# Sheet2.net
KiCad netlist of a schematic drawn in Altium Designer
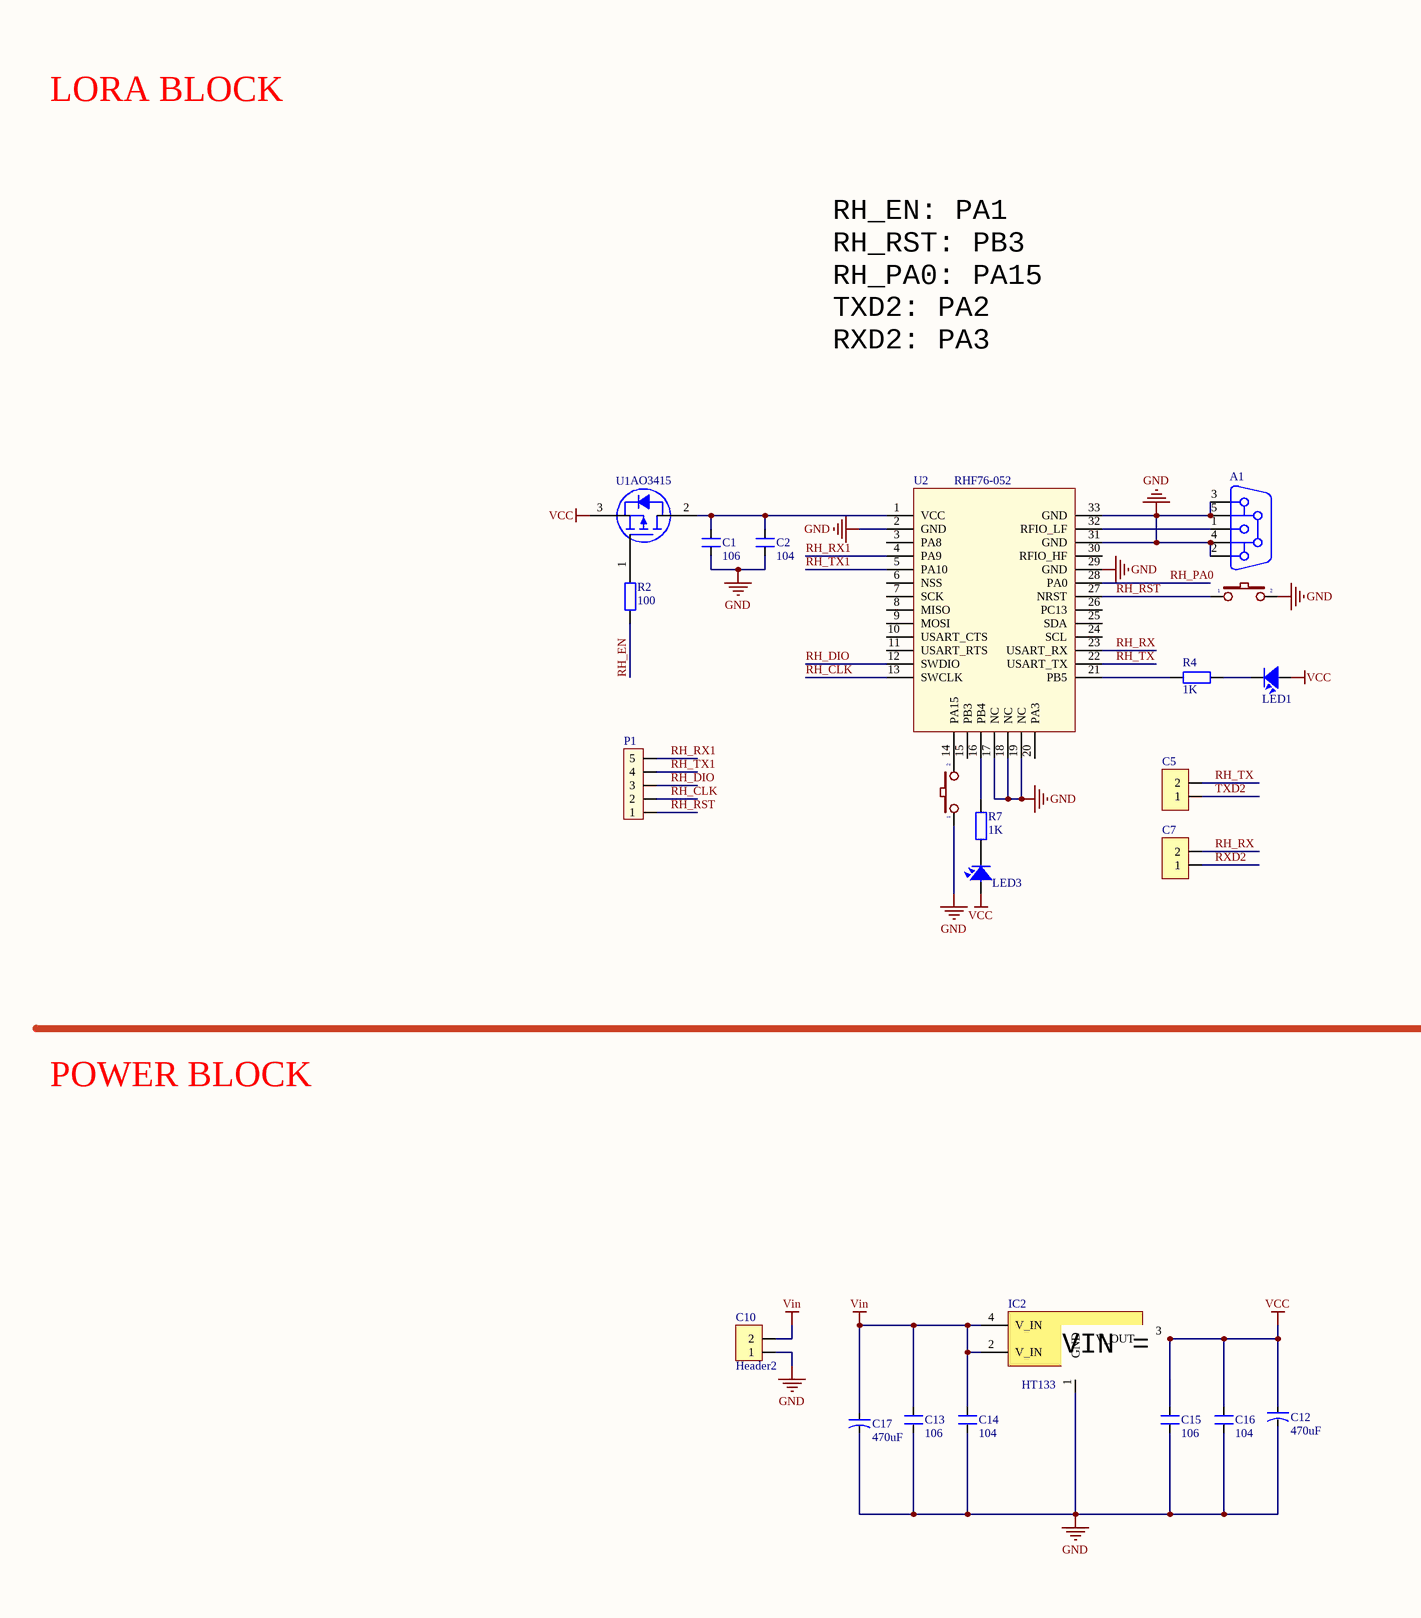
[diagram p0: Sheet2.SchDoc, left]
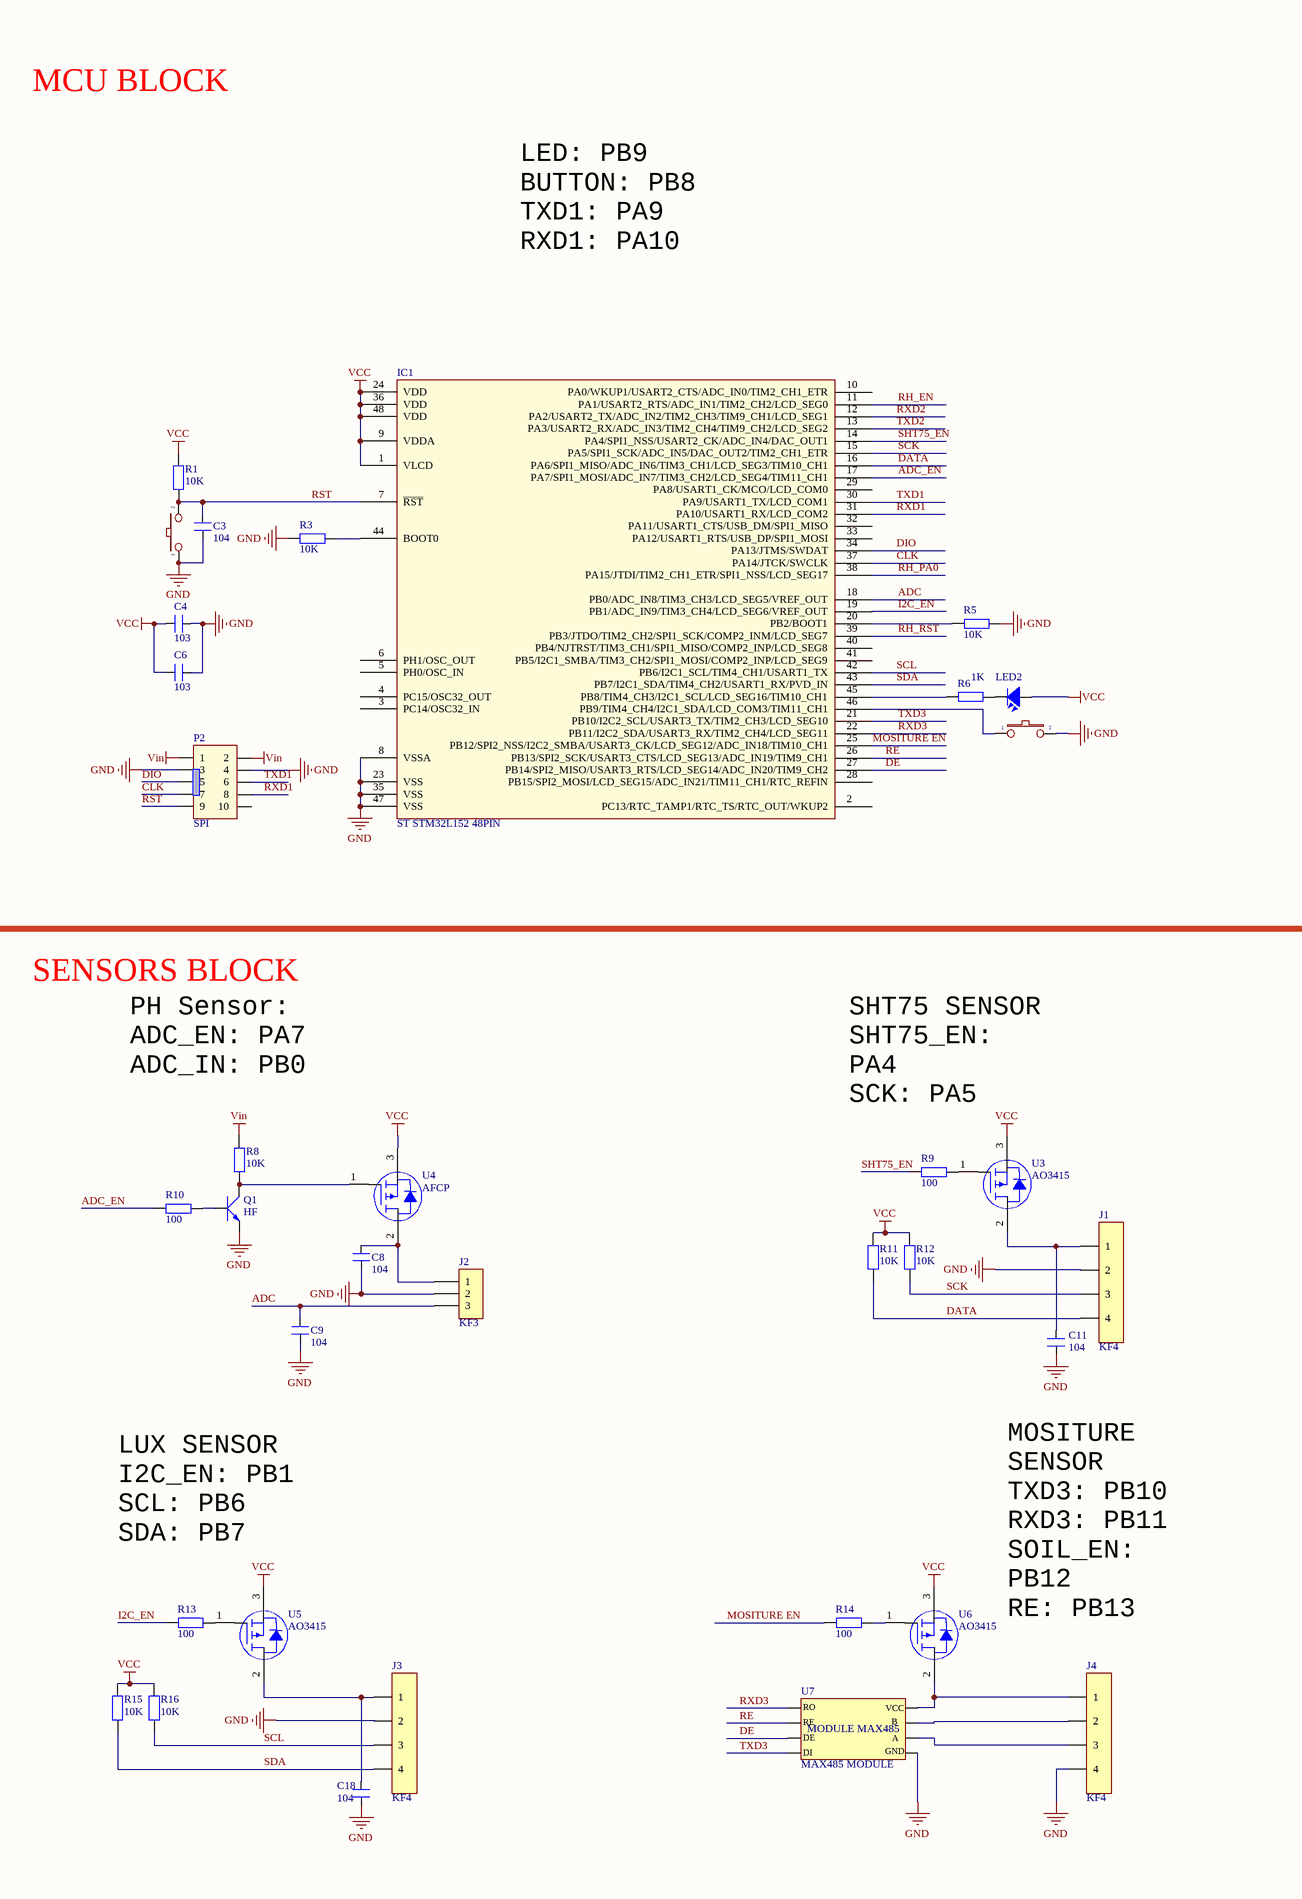
[diagram p1: Sheet2.SchDoc, right]

(export (version "E")
  (design (tool "Eeschema 10.0.6"))
  (components
    (comp (ref "A1")
      (value "~")
      (footprint "SMA-V")
      (description "CONNECTOR ANTEN")
      (fields
        (field (name "PARTNO") "210111003")
        (field (name "MANUFACTURER") "Würth Elektronik eiSos GmbH")
        (field (name "CREATED BY") "Christin Zierenner")
      )
      (libsource (lib "LIBRARY") (part "CON Ant"))
    )
    (comp (ref "C1")
      (value "106")
      (footprint "CAP 0805")
      (description "Cap SMD")
      (libsource (lib "linhkien69") (part "CM"))
    )
    (comp (ref "C2")
      (value "104")
      (footprint "CAP 0805")
      (description "Cap SMD")
      (libsource (lib "linhkien69") (part "CM"))
    )
    (comp (ref "C3")
      (value "104")
      (footprint "CAP 0805")
      (description "Cap SMD")
      (libsource (lib "linhkien69") (part "CM"))
    )
    (comp (ref "C4")
      (value "103")
      (footprint "CAP 0805")
      (description "Cap SMD")
      (libsource (lib "linhkien69") (part "CM"))
    )
    (comp (ref "C5")
      (value "JP2")
      (footprint "JP2-CLOSED")
      (description "WR-PHD 2.54 mm Angled Socket Header")
      (fields
        (field (name "MANUFACTURER") "Würth Elektronik eiSos GmbH")
        (field (name "PARTNO") "613002143121")
        (field (name "CREATED BY") "Karrer Zheng")
      )
      (libsource (lib "LIBRARY") (part "JP2"))
    )
    (comp (ref "C6")
      (value "103")
      (footprint "CAP 0805")
      (description "Cap SMD")
      (libsource (lib "linhkien69") (part "CM"))
    )
    (comp (ref "C7")
      (value "JP2")
      (footprint "JP2-CLOSED")
      (description "WR-PHD 2.54 mm Angled Socket Header")
      (fields
        (field (name "MANUFACTURER") "Würth Elektronik eiSos GmbH")
        (field (name "PARTNO") "613002143121")
        (field (name "CREATED BY") "Karrer Zheng")
      )
      (libsource (lib "LIBRARY") (part "JP2"))
    )
    (comp (ref "C8")
      (value "104")
      (footprint "CAP 0805")
      (description "Cap SMD")
      (libsource (lib "linhkien69") (part "CM"))
    )
    (comp (ref "C9")
      (value "104")
      (footprint "CAP 0805")
      (description "Cap SMD")
      (libsource (lib "linhkien69") (part "CM"))
    )
    (comp (ref "C10")
      (value "Header2")
      (footprint "Header2")
      (description "Header IDC, 2 x 1 Pin Vertical 2.54mm Pitch (Non-Boxed, Male)")
      (fields
        (field (name "MANUFACTURER") "Würth Elektronik eiSos GmbH")
        (field (name "PARTNO") "613002143121")
        (field (name "CREATED BY") "Karrer Zheng")
      )
      (libsource (lib "LIBRARY") (part "Header2"))
    )
    (comp (ref "C11")
      (value "104")
      (footprint "CAP 0805")
      (description "Cap SMD")
      (libsource (lib "linhkien69") (part "CM"))
    )
    (comp (ref "C12")
      (value "470uF")
      (footprint "Tu_Nhom")
      (description "Polarized Capacitor (Axial)")
      (fields (field (name "PUBLISHER") "Altium Limited"))
      (libsource (lib "LIBRARY") (part "CN-ALU-SMD"))
    )
    (comp (ref "C13")
      (value "106")
      (footprint "CAP 0805")
      (description "Cap SMD")
      (libsource (lib "linhkien69") (part "CM"))
    )
    (comp (ref "C14")
      (value "104")
      (footprint "CAP 0805")
      (description "Cap SMD")
      (libsource (lib "linhkien69") (part "CM"))
    )
    (comp (ref "C15")
      (value "106")
      (footprint "CAP 0805")
      (description "Cap SMD")
      (libsource (lib "linhkien69") (part "CM"))
    )
    (comp (ref "C16")
      (value "104")
      (footprint "CAP 0805")
      (description "Cap SMD")
      (libsource (lib "linhkien69") (part "CM"))
    )
    (comp (ref "C17")
      (value "470uF")
      (footprint "Tu_Nhom")
      (description "Polarized Capacitor (Axial)")
      (fields (field (name "PUBLISHER") "Altium Limited"))
      (libsource (lib "LIBRARY") (part "CN-ALU-SMD"))
    )
    (comp (ref "C18")
      (value "104")
      (footprint "CAP 0805")
      (description "Cap SMD")
      (libsource (lib "linhkien69") (part "CM"))
    )
    (comp (ref "IC1")
      (value "ST STM32L152 48PIN")
      (footprint "ST LQFP-48 7x7MM")
      (libsource (lib "DEV_lib") (part "ST STM32L152 48PIN"))
    )
    (comp (ref "IC2")
      (value "HT133")
      (footprint "HT7133")
      (description "HT73XX")
      (libsource (lib "DEV_lib") (part "HT73XX_1"))
    )
    (comp (ref "J1")
      (value "KF4")
      (footprint "KF4")
      (fields
        (field (name "MANUFACTURER") "Würth Elektronik eiSos GmbH")
        (field (name "PARTNO") "691133710004")
        (field (name "CREATED BY") "Baojun Chen")
      )
      (libsource (lib "DEV_lib") (part "KF4"))
    )
    (comp (ref "J2")
      (value "KF3")
      (footprint "KF3-5.08T")
      (fields
        (field (name "MANUFACTURER") "Würth Elektronik eiSos GmbH")
        (field (name "PARTNO") "691103110003")
        (field (name "CREATED BY") "Karrer Zheng")
      )
      (libsource (lib "LIBRARY") (part "KF3"))
    )
    (comp (ref "J3")
      (value "KF4")
      (footprint "KF4")
      (fields
        (field (name "MANUFACTURER") "Würth Elektronik eiSos GmbH")
        (field (name "PARTNO") "691133710004")
        (field (name "CREATED BY") "Baojun Chen")
      )
      (libsource (lib "DEV_lib") (part "KF4"))
    )
    (comp (ref "J4")
      (value "KF4")
      (footprint "KF4")
      (fields
        (field (name "MANUFACTURER") "Würth Elektronik eiSos GmbH")
        (field (name "PARTNO") "691133710004")
        (field (name "CREATED BY") "Baojun Chen")
      )
      (libsource (lib "DEV_lib") (part "KF4"))
    )
    (comp (ref "LED1") (value "LED") (footprint "LED 0805") (libsource (lib "LIBRARY") (part "LED SMD")))
    (comp (ref "LED2") (value "LED") (footprint "Header2") (libsource (lib "LIBRARY") (part "LED SMD")))
    (comp (ref "LED3") (value "LED") (footprint "LED 0805") (libsource (lib "LIBRARY") (part "LED SMD")))
    (comp (ref "P1") (value "JP5") (footprint "JP5") (libsource (lib "linhkien69") (part "JP5")))
    (comp (ref "P2")
      (value "SPI")
      (footprint "IDE_2X5")
      (description "Header 5x2")
      (libsource (lib "linhkien69") (part "IDE 5x2"))
    )
    (comp (ref "Q1")
      (value "HF")
      (footprint "SOT23B")
      (description "NPN 600mW, ECB")
      (libsource (lib "linhkien69") (part "C1815"))
    )
    (comp (ref "R1")
      (value "10K")
      (footprint "RES 0805/2012")
      (description "Resistor SMD")
      (libsource (lib "linhkien69") (part "RM"))
    )
    (comp (ref "R2")
      (value "100")
      (footprint "RES 0805/2012")
      (description "Resistor SMD")
      (libsource (lib "linhkien69") (part "RM"))
    )
    (comp (ref "R3")
      (value "10K")
      (footprint "RES 0805/2012")
      (description "Resistor SMD")
      (libsource (lib "linhkien69") (part "RM"))
    )
    (comp (ref "R4")
      (value "1K")
      (footprint "RES 0805/2012")
      (description "Resistor SMD")
      (libsource (lib "linhkien69") (part "RM"))
    )
    (comp (ref "R5")
      (value "10K")
      (footprint "RES 0805/2012")
      (description "Resistor SMD")
      (libsource (lib "linhkien69") (part "RM"))
    )
    (comp (ref "R6")
      (value "1K")
      (footprint "RES 0805/2012")
      (description "Resistor SMD")
      (libsource (lib "linhkien69") (part "RM"))
    )
    (comp (ref "R7")
      (value "1K")
      (footprint "RES 0805/2012")
      (description "Resistor SMD")
      (libsource (lib "linhkien69") (part "RM"))
    )
    (comp (ref "R8")
      (value "10K")
      (footprint "RES 0805/2012")
      (description "Resistor SMD")
      (libsource (lib "linhkien69") (part "RM"))
    )
    (comp (ref "R9")
      (value "100")
      (footprint "RES 0805/2012")
      (description "Resistor SMD")
      (libsource (lib "linhkien69") (part "RM"))
    )
    (comp (ref "R10")
      (value "100")
      (footprint "RES 0805/2012")
      (description "Resistor SMD")
      (libsource (lib "linhkien69") (part "RM"))
    )
    (comp (ref "R11")
      (value "10K")
      (footprint "RES 0805/2012")
      (description "Resistor SMD")
      (libsource (lib "linhkien69") (part "RM"))
    )
    (comp (ref "R12")
      (value "10K")
      (footprint "RES 0805/2012")
      (description "Resistor SMD")
      (libsource (lib "linhkien69") (part "RM"))
    )
    (comp (ref "R13")
      (value "100")
      (footprint "RES 0805/2012")
      (description "Resistor SMD")
      (libsource (lib "linhkien69") (part "RM"))
    )
    (comp (ref "R14")
      (value "100")
      (footprint "RES 0805/2012")
      (description "Resistor SMD")
      (libsource (lib "linhkien69") (part "RM"))
    )
    (comp (ref "R15")
      (value "10K")
      (footprint "RES 0805/2012")
      (description "Resistor SMD")
      (libsource (lib "linhkien69") (part "RM"))
    )
    (comp (ref "R16")
      (value "10K")
      (footprint "RES 0805/2012")
      (description "Resistor SMD")
      (libsource (lib "linhkien69") (part "RM"))
    )
    (comp (ref "SW1")
      (value "LRST")
      (footprint "SW1-SMD")
      (description "Switch button 2 pin")
      (libsource (lib "linhkien69") (part "SW2"))
    )
    (comp (ref "SW2")
      (value "RST")
      (footprint "Header2")
      (description "Switch button 2 pin")
      (libsource (lib "linhkien69") (part "SW2"))
    )
    (comp (ref "SW3")
      (value "DFU")
      (footprint "SW1-SMD")
      (description "Switch button 2 pin")
      (libsource (lib "linhkien69") (part "SW2"))
    )
    (comp (ref "SW4")
      (value "RST")
      (footprint "Header2")
      (description "Switch button 2 pin")
      (libsource (lib "linhkien69") (part "SW2"))
    )
    (comp (ref "U1") (value "AO3415") (footprint "SOT23B") (libsource (lib "linhkien69") (part "AO3415")))
    (comp (ref "U2")
      (value "RHF76-052")
      (footprint "RHF76-052")
      (libsource (lib "RHF76-052") (part "RHF76-052"))
    )
    (comp (ref "U3") (value "AO3415") (footprint "SOT23B") (libsource (lib "linhkien69") (part "AO3415")))
    (comp (ref "U4") (value "AFCP") (footprint "SOT23B") (libsource (lib "linhkien69") (part "AO3415")))
    (comp (ref "U5") (value "AO3415") (footprint "SOT23B") (libsource (lib "linhkien69") (part "AO3415")))
    (comp (ref "U6") (value "AO3415") (footprint "SOT23B") (libsource (lib "linhkien69") (part "AO3415")))
    (comp (ref "U7")
      (value "MAX485 MODULE")
      (footprint "MODULE MAX485")
      (libsource (lib "DEV_lib") (part "MAX485 MODULE"))
    )
  )
  (nets
    (net (code "1") (name "/ADC") (class "Default")
      (node (ref "C9") (pin "1") (pinfunction "1_1") (pintype "passive"))
      (node (ref "IC1") (pin "18") (pinfunction "PB0/ADC_IN8/TIM3_CH3/LCD_SEG5/VREF_OUT_18") (pintype "passive"))
      (node (ref "J2") (pin "3") (pinfunction "3_3") (pintype "passive"))
    )
    (net (code "2") (name "/ADC_EN") (class "Default")
      (node (ref "IC1") (pin "17") (pinfunction "PA7/SPI1_MOSI/ADC_IN7/TIM3_CH2/LCD_SEG4/TIM11_CH1_17") (pintype "passive"))
      (node (ref "R10") (pin "2") (pinfunction "2_2") (pintype "passive"))
    )
    (net (code "3") (name "/CLK") (class "Default")
      (node (ref "IC1") (pin "37") (pinfunction "PA14/JTCK/SWCLK_37") (pintype "passive"))
      (node (ref "P2") (pin "7") (pinfunction "7_7") (pintype "passive"))
    )
    (net (code "4") (name "/DATA") (class "Default")
      (node (ref "IC1") (pin "16") (pinfunction "PA6/SPI1_MISO/ADC_IN6/TIM3_CH1/LCD_SEG3/TIM10_CH1_16") (pintype "passive"))
      (node (ref "J1") (pin "4") (pinfunction "4_4") (pintype "passive"))
      (node (ref "R11") (pin "1") (pinfunction "1_1") (pintype "passive"))
    )
    (net (code "5") (name "/DE") (class "Default")
      (node (ref "IC1") (pin "27") (pinfunction "PB14/SPI2_MISO/USART3_RTS/LCD_SEG14/ADC_IN20/TIM9_CH2_27") (pintype "passive"))
      (node (ref "U7") (pin "3") (pinfunction "3_3") (pintype "passive"))
    )
    (net (code "6") (name "/DIO") (class "Default")
      (node (ref "IC1") (pin "34") (pinfunction "PA13/JTMS/SWDAT_34") (pintype "passive"))
      (node (ref "P2") (pin "5") (pinfunction "5_5") (pintype "passive"))
    )
    (net (code "7") (name "/I2C_EN") (class "Default")
      (node (ref "IC1") (pin "19") (pinfunction "PB1/ADC_IN9/TIM3_CH4/LCD_SEG6/VREF_OUT_19") (pintype "passive"))
      (node (ref "R13") (pin "2") (pinfunction "2_2") (pintype "passive"))
    )
    (net (code "8") (name "/MOSITURE EN") (class "Default")
      (node (ref "IC1") (pin "25") (pinfunction "PB12/SPI2_NSS/I2C2_SMBA/USART3_CK/LCD_SEG12/ADC_IN18/TIM10_CH1_25") (pintype "passive"))
      (node (ref "R14") (pin "2") (pinfunction "2_2") (pintype "passive"))
    )
    (net (code "9") (name "/RE") (class "Default")
      (node (ref "IC1") (pin "26") (pinfunction "PB13/SPI2_SCK/USART3_CTS/LCD_SEG13/ADC_IN19/TIM9_CH1_26") (pintype "passive"))
      (node (ref "U7") (pin "2") (pinfunction "2_2") (pintype "passive"))
    )
    (net (code "10") (name "/RH_CLK") (class "Default")
      (node (ref "P1") (pin "2") (pinfunction "2_2") (pintype "passive"))
      (node (ref "U2") (pin "13") (pinfunction "SWCLK_13") (pintype "passive"))
    )
    (net (code "11") (name "/RH_DIO") (class "Default")
      (node (ref "P1") (pin "3") (pinfunction "3_3") (pintype "passive"))
      (node (ref "U2") (pin "12") (pinfunction "SWDIO_12") (pintype "passive"))
    )
    (net (code "12") (name "/RH_EN") (class "Default")
      (node (ref "IC1") (pin "11") (pinfunction "PA1/USART2_RTS/ADC_IN1/TIM2_CH2/LCD_SEG0_11") (pintype "passive"))
      (node (ref "R2") (pin "2") (pinfunction "2_2") (pintype "passive"))
    )
    (net (code "13") (name "/RH_PA0") (class "Default")
      (node (ref "IC1") (pin "38") (pinfunction "PA15/JTDI/TIM2_CH1_ETR/SPI1_NSS/LCD_SEG17_38") (pintype "passive"))
      (node (ref "U2") (pin "28") (pinfunction "PA0_28") (pintype "passive"))
    )
    (net (code "14") (name "/RH_RST") (class "Default")
      (node (ref "IC1") (pin "39") (pinfunction "PB3/JTDO/TIM2_CH2/SPI1_SCK/COMP2_INM/LCD_SEG7_39") (pintype "passive"))
      (node (ref "P1") (pin "1") (pinfunction "1_1") (pintype "passive"))
      (node (ref "SW1") (pin "1") (pinfunction "1_1") (pintype "passive"))
      (node (ref "U2") (pin "27") (pinfunction "NRST_27") (pintype "passive"))
    )
    (net (code "15") (name "/RH_RX") (class "Default")
      (node (ref "C7") (pin "2") (pinfunction "2_2") (pintype "passive"))
      (node (ref "U2") (pin "23") (pinfunction "USART_RX_23") (pintype "passive"))
    )
    (net (code "16") (name "/RH_RX1") (class "Default")
      (node (ref "P1") (pin "5") (pinfunction "5_5") (pintype "passive"))
      (node (ref "U2") (pin "4") (pinfunction "PA9_4") (pintype "passive"))
    )
    (net (code "17") (name "/RH_TX") (class "Default")
      (node (ref "C5") (pin "2") (pinfunction "2_2") (pintype "passive"))
      (node (ref "U2") (pin "22") (pinfunction "USART_TX_22") (pintype "passive"))
    )
    (net (code "18") (name "/RH_TX1") (class "Default")
      (node (ref "P1") (pin "4") (pinfunction "4_4") (pintype "passive"))
      (node (ref "U2") (pin "5") (pinfunction "PA10_5") (pintype "passive"))
    )
    (net (code "19") (name "/RST") (class "Default")
      (node (ref "C3") (pin "2") (pinfunction "2_2") (pintype "passive"))
      (node (ref "IC1") (pin "7") (pinfunction "~{RST}_7") (pintype "passive"))
      (node (ref "P2") (pin "9") (pinfunction "9_9") (pintype "passive"))
      (node (ref "R1") (pin "1") (pinfunction "1_1") (pintype "passive"))
      (node (ref "SW2") (pin "2") (pinfunction "2_2") (pintype "passive"))
    )
    (net (code "20") (name "/RXD1") (class "Default")
      (node (ref "IC1") (pin "31") (pinfunction "PA10/USART1_RX/LCD_COM2_31") (pintype "passive"))
      (node (ref "P2") (pin "8") (pinfunction "8_8") (pintype "passive"))
    )
    (net (code "21") (name "/RXD2") (class "Default")
      (node (ref "C7") (pin "1") (pinfunction "1_1") (pintype "passive"))
      (node (ref "IC1") (pin "12") (pinfunction "PA2/USART2_TX/ADC_IN2/TIM2_CH3/TIM9_CH1/LCD_SEG1_12") (pintype "passive"))
    )
    (net (code "22") (name "/RXD3") (class "Default")
      (node (ref "IC1") (pin "22") (pinfunction "PB11/I2C2_SDA/USART3_RX/TIM2_CH4/LCD_SEG11_22") (pintype "passive"))
      (node (ref "U7") (pin "1") (pinfunction "1_1") (pintype "passive"))
    )
    (net (code "23") (name "/SCK") (class "Default")
      (node (ref "IC1") (pin "15") (pinfunction "PA5/SPI1_SCK/ADC_IN5/DAC_OUT2/TIM2_CH1_ETR_15") (pintype "passive"))
      (node (ref "J1") (pin "3") (pinfunction "3_3") (pintype "passive"))
      (node (ref "R12") (pin "1") (pinfunction "1_1") (pintype "passive"))
    )
    (net (code "24") (name "/SCL") (class "Default")
      (node (ref "IC1") (pin "42") (pinfunction "PB6/I2C1_SCL/TIM4_CH1/USART1_TX_42") (pintype "passive"))
      (node (ref "J3") (pin "3") (pinfunction "3_3") (pintype "passive"))
      (node (ref "R16") (pin "1") (pinfunction "1_1") (pintype "passive"))
    )
    (net (code "25") (name "/SDA") (class "Default")
      (node (ref "IC1") (pin "43") (pinfunction "PB7/I2C1_SDA/TIM4_CH2/USART1_RX/PVD_IN_43") (pintype "passive"))
      (node (ref "J3") (pin "4") (pinfunction "4_4") (pintype "passive"))
      (node (ref "R15") (pin "1") (pinfunction "1_1") (pintype "passive"))
    )
    (net (code "26") (name "/SHT75_EN") (class "Default")
      (node (ref "IC1") (pin "14") (pinfunction "PA4/SPI1_NSS/USART2_CK/ADC_IN4/DAC_OUT1_14") (pintype "passive"))
      (node (ref "R9") (pin "2") (pinfunction "2_2") (pintype "passive"))
    )
    (net (code "27") (name "/TXD1") (class "Default")
      (node (ref "IC1") (pin "30") (pinfunction "PA9/USART1_TX/LCD_COM1_30") (pintype "passive"))
      (node (ref "P2") (pin "6") (pinfunction "6_6") (pintype "passive"))
    )
    (net (code "28") (name "/TXD2") (class "Default")
      (node (ref "C5") (pin "1") (pinfunction "1_1") (pintype "passive"))
      (node (ref "IC1") (pin "13") (pinfunction "PA3/USART2_RX/ADC_IN3/TIM2_CH4/TIM9_CH2/LCD_SEG2_13") (pintype "passive"))
    )
    (net (code "29") (name "/TXD3") (class "Default")
      (node (ref "IC1") (pin "21") (pinfunction "PB10/I2C2_SCL/USART3_TX/TIM2_CH3/LCD_SEG10_21") (pintype "passive"))
      (node (ref "U7") (pin "4") (pinfunction "4_4") (pintype "passive"))
    )
    (net (code "30") (name "GND") (class "Default")
      (node (ref "A1") (pin "2") (pinfunction "2_2") (pintype "passive"))
      (node (ref "A1") (pin "3") (pinfunction "3_3") (pintype "passive"))
      (node (ref "A1") (pin "4") (pinfunction "4_4") (pintype "passive"))
      (node (ref "A1") (pin "5") (pinfunction "5_5") (pintype "passive"))
      (node (ref "C1") (pin "2") (pinfunction "2_2") (pintype "passive"))
      (node (ref "C10") (pin "1") (pinfunction "1_1") (pintype "passive"))
      (node (ref "C11") (pin "2") (pinfunction "2_2") (pintype "passive"))
      (node (ref "C12") (pin "2") (pinfunction "2_2") (pintype "passive"))
      (node (ref "C13") (pin "2") (pinfunction "2_2") (pintype "passive"))
      (node (ref "C14") (pin "2") (pinfunction "2_2") (pintype "passive"))
      (node (ref "C15") (pin "2") (pinfunction "2_2") (pintype "passive"))
      (node (ref "C16") (pin "2") (pinfunction "2_2") (pintype "passive"))
      (node (ref "C17") (pin "2") (pinfunction "2_2") (pintype "passive"))
      (node (ref "C18") (pin "2") (pinfunction "2_2") (pintype "passive"))
      (node (ref "C2") (pin "1") (pinfunction "1_1") (pintype "passive"))
      (node (ref "C3") (pin "1") (pinfunction "1_1") (pintype "passive"))
      (node (ref "C4") (pin "2") (pinfunction "2_2") (pintype "passive"))
      (node (ref "C6") (pin "2") (pinfunction "2_2") (pintype "passive"))
      (node (ref "C8") (pin "2") (pinfunction "2_2") (pintype "passive"))
      (node (ref "C9") (pin "2") (pinfunction "2_2") (pintype "passive"))
      (node (ref "IC1") (pin "23") (pinfunction "VSS_23") (pintype "passive"))
      (node (ref "IC1") (pin "35") (pinfunction "VSS_35") (pintype "passive"))
      (node (ref "IC1") (pin "47") (pinfunction "VSS_47") (pintype "passive"))
      (node (ref "IC1") (pin "8") (pinfunction "VSSA_8") (pintype "passive"))
      (node (ref "IC2") (pin "1") (pinfunction "GND_1") (pintype "passive"))
      (node (ref "J1") (pin "2") (pinfunction "2_2") (pintype "passive"))
      (node (ref "J2") (pin "2") (pinfunction "2_2") (pintype "passive"))
      (node (ref "J3") (pin "2") (pinfunction "2_2") (pintype "passive"))
      (node (ref "J4") (pin "4") (pinfunction "4_4") (pintype "passive"))
      (node (ref "P2") (pin "3") (pinfunction "3_3") (pintype "passive"))
      (node (ref "P2") (pin "4") (pinfunction "4_4") (pintype "passive"))
      (node (ref "Q1") (pin "1") (pinfunction "E_1") (pintype "passive"))
      (node (ref "R3") (pin "1") (pinfunction "1_1") (pintype "passive"))
      (node (ref "R5") (pin "2") (pinfunction "2_2") (pintype "passive"))
      (node (ref "SW1") (pin "2") (pinfunction "2_2") (pintype "passive"))
      (node (ref "SW2") (pin "1") (pinfunction "1_1") (pintype "passive"))
      (node (ref "SW3") (pin "1") (pinfunction "1_1") (pintype "passive"))
      (node (ref "SW4") (pin "2") (pinfunction "2_2") (pintype "passive"))
      (node (ref "U2") (pin "17") (pinfunction "NC_17") (pintype "passive"))
      (node (ref "U2") (pin "18") (pinfunction "NC_18") (pintype "passive"))
      (node (ref "U2") (pin "19") (pinfunction "NC_19") (pintype "passive"))
      (node (ref "U2") (pin "2") (pinfunction "GND_2") (pintype "passive"))
      (node (ref "U2") (pin "29") (pinfunction "GND_29") (pintype "passive"))
      (node (ref "U2") (pin "31") (pinfunction "GND_31") (pintype "passive"))
      (node (ref "U2") (pin "33") (pinfunction "GND_33") (pintype "passive"))
      (node (ref "U7") (pin "5") (pinfunction "5_5") (pintype "passive"))
    )
    (net (code "31") (name "Net-(IC1-BOOT0)") (class "Default")
      (node (ref "IC1") (pin "44") (pinfunction "BOOT0_44") (pintype "passive"))
      (node (ref "R3") (pin "2") (pinfunction "2_2") (pintype "passive"))
    )
    (net (code "32") (name "Net-(IC1-PB2{slash}BOOT1)") (class "Default")
      (node (ref "IC1") (pin "20") (pinfunction "PB2/BOOT1_20") (pintype "passive"))
      (node (ref "R5") (pin "1") (pinfunction "1_1") (pintype "passive"))
    )
    (net (code "33") (name "Net-(IC1-PB8{slash}TIM4_CH3{slash}I2C1_SCL{slash}LCD_SEG16{slash}TIM10_CH1)") (class "Default")
      (node (ref "IC1") (pin "45") (pinfunction "PB8/TIM4_CH3/I2C1_SCL/LCD_SEG16/TIM10_CH1_45") (pintype "passive"))
      (node (ref "R6") (pin "1") (pinfunction "1_1") (pintype "passive"))
    )
    (net (code "34") (name "Net-(IC1-PB9{slash}TIM4_CH4{slash}I2C1_SDA{slash}LCD_COM3{slash}TIM11_CH1)") (class "Default")
      (node (ref "IC1") (pin "46") (pinfunction "PB9/TIM4_CH4/I2C1_SDA/LCD_COM3/TIM11_CH1_46") (pintype "passive"))
      (node (ref "SW4") (pin "1") (pinfunction "1_1") (pintype "passive"))
    )
    (net (code "35") (name "Net-(J4-Pad2)") (class "Default")
      (node (ref "J4") (pin "2") (pinfunction "2_2") (pintype "passive"))
      (node (ref "U7") (pin "7") (pinfunction "7_7") (pintype "passive"))
    )
    (net (code "36") (name "Net-(J4-Pad3)") (class "Default")
      (node (ref "J4") (pin "3") (pinfunction "3_3") (pintype "passive"))
      (node (ref "U7") (pin "6") (pinfunction "6_6") (pintype "passive"))
    )
    (net (code "37") (name "Net-(LED1-Pad2)") (class "Default")
      (node (ref "LED1") (pin "2") (pinfunction "2_2") (pintype "passive"))
      (node (ref "R4") (pin "2") (pinfunction "2_2") (pintype "passive"))
    )
    (net (code "38") (name "Net-(LED2-Pad2)") (class "Default")
      (node (ref "LED2") (pin "2") (pinfunction "2_2") (pintype "passive"))
      (node (ref "R6") (pin "2") (pinfunction "2_2") (pintype "passive"))
    )
    (net (code "39") (name "Net-(LED3-Pad2)") (class "Default")
      (node (ref "LED3") (pin "2") (pinfunction "2_2") (pintype "passive"))
      (node (ref "R7") (pin "2") (pinfunction "2_2") (pintype "passive"))
    )
    (net (code "40") (name "Net-(Q1-B)") (class "Default")
      (node (ref "Q1") (pin "3") (pinfunction "B_3") (pintype "passive"))
      (node (ref "R10") (pin "1") (pinfunction "1_1") (pintype "passive"))
    )
    (net (code "41") (name "Net-(Q1-C)") (class "Default")
      (node (ref "Q1") (pin "2") (pinfunction "C_2") (pintype "passive"))
      (node (ref "R8") (pin "1") (pinfunction "1_1") (pintype "passive"))
      (node (ref "U4") (pin "1") (pinfunction "G_1") (pintype "passive"))
    )
    (net (code "42") (name "Net-(U1-D)") (class "Default")
      (node (ref "C1") (pin "1") (pinfunction "1_1") (pintype "passive"))
      (node (ref "C2") (pin "2") (pinfunction "2_2") (pintype "passive"))
      (node (ref "U1") (pin "2") (pinfunction "D_2") (pintype "passive"))
      (node (ref "U2") (pin "1") (pinfunction "VCC_1") (pintype "passive"))
    )
    (net (code "43") (name "Net-(U1-G)") (class "Default")
      (node (ref "R2") (pin "1") (pinfunction "1_1") (pintype "passive"))
      (node (ref "U1") (pin "1") (pinfunction "G_1") (pintype "passive"))
    )
    (net (code "44") (name "Net-(U2-PA15)") (class "Default")
      (node (ref "SW3") (pin "2") (pinfunction "2_2") (pintype "passive"))
      (node (ref "U2") (pin "14") (pinfunction "PA15_14") (pintype "passive"))
    )
    (net (code "45") (name "Net-(U2-PB4)") (class "Default")
      (node (ref "R7") (pin "1") (pinfunction "1_1") (pintype "passive"))
      (node (ref "U2") (pin "16") (pinfunction "PB4_16") (pintype "passive"))
    )
    (net (code "46") (name "Net-(U2-PB5)") (class "Default")
      (node (ref "R4") (pin "1") (pinfunction "1_1") (pintype "passive"))
      (node (ref "U2") (pin "21") (pinfunction "PB5_21") (pintype "passive"))
    )
    (net (code "47") (name "Net-(U2-RFIO_LF)") (class "Default")
      (node (ref "A1") (pin "1") (pinfunction "1_1") (pintype "passive"))
      (node (ref "U2") (pin "32") (pinfunction "RFIO_LF_32") (pintype "passive"))
    )
    (net (code "48") (name "Net-(U3-D)") (class "Default")
      (node (ref "C11") (pin "1") (pinfunction "1_1") (pintype "passive"))
      (node (ref "J1") (pin "1") (pinfunction "1_1") (pintype "passive"))
      (node (ref "U3") (pin "2") (pinfunction "D_2") (pintype "passive"))
    )
    (net (code "49") (name "Net-(U3-G)") (class "Default")
      (node (ref "R9") (pin "1") (pinfunction "1_1") (pintype "passive"))
      (node (ref "U3") (pin "1") (pinfunction "G_1") (pintype "passive"))
    )
    (net (code "50") (name "Net-(U4-D)") (class "Default")
      (node (ref "C8") (pin "1") (pinfunction "1_1") (pintype "passive"))
      (node (ref "J2") (pin "1") (pinfunction "1_1") (pintype "passive"))
      (node (ref "U4") (pin "2") (pinfunction "D_2") (pintype "passive"))
    )
    (net (code "51") (name "Net-(U5-D)") (class "Default")
      (node (ref "C18") (pin "1") (pinfunction "1_1") (pintype "passive"))
      (node (ref "J3") (pin "1") (pinfunction "1_1") (pintype "passive"))
      (node (ref "U5") (pin "2") (pinfunction "D_2") (pintype "passive"))
    )
    (net (code "52") (name "Net-(U5-G)") (class "Default")
      (node (ref "R13") (pin "1") (pinfunction "1_1") (pintype "passive"))
      (node (ref "U5") (pin "1") (pinfunction "G_1") (pintype "passive"))
    )
    (net (code "53") (name "Net-(U6-D)") (class "Default")
      (node (ref "J4") (pin "1") (pinfunction "1_1") (pintype "passive"))
      (node (ref "U6") (pin "2") (pinfunction "D_2") (pintype "passive"))
      (node (ref "U7") (pin "8") (pinfunction "8_8") (pintype "passive"))
    )
    (net (code "54") (name "Net-(U6-G)") (class "Default")
      (node (ref "R14") (pin "1") (pinfunction "1_1") (pintype "passive"))
      (node (ref "U6") (pin "1") (pinfunction "G_1") (pintype "passive"))
    )
    (net (code "55") (name "VCC") (class "Default")
      (node (ref "C12") (pin "1") (pinfunction "1_1") (pintype "passive"))
      (node (ref "C15") (pin "1") (pinfunction "1_1") (pintype "passive"))
      (node (ref "C16") (pin "1") (pinfunction "1_1") (pintype "passive"))
      (node (ref "C4") (pin "1") (pinfunction "1_1") (pintype "passive"))
      (node (ref "C6") (pin "1") (pinfunction "1_1") (pintype "passive"))
      (node (ref "IC1") (pin "1") (pinfunction "VLCD_1") (pintype "passive"))
      (node (ref "IC1") (pin "24") (pinfunction "VDD_24") (pintype "passive"))
      (node (ref "IC1") (pin "36") (pinfunction "VDD_36") (pintype "passive"))
      (node (ref "IC1") (pin "48") (pinfunction "VDD_48") (pintype "passive"))
      (node (ref "IC1") (pin "9") (pinfunction "VDDA_9") (pintype "passive"))
      (node (ref "IC2") (pin "3") (pinfunction "V_OUT_3") (pintype "passive"))
      (node (ref "LED1") (pin "1") (pinfunction "1_1") (pintype "passive"))
      (node (ref "LED2") (pin "1") (pinfunction "1_1") (pintype "passive"))
      (node (ref "LED3") (pin "1") (pinfunction "1_1") (pintype "passive"))
      (node (ref "R1") (pin "2") (pinfunction "2_2") (pintype "passive"))
      (node (ref "R11") (pin "2") (pinfunction "2_2") (pintype "passive"))
      (node (ref "R12") (pin "2") (pinfunction "2_2") (pintype "passive"))
      (node (ref "R15") (pin "2") (pinfunction "2_2") (pintype "passive"))
      (node (ref "R16") (pin "2") (pinfunction "2_2") (pintype "passive"))
      (node (ref "U1") (pin "3") (pinfunction "S_3") (pintype "passive"))
      (node (ref "U3") (pin "3") (pinfunction "S_3") (pintype "passive"))
      (node (ref "U4") (pin "3") (pinfunction "S_3") (pintype "passive"))
      (node (ref "U5") (pin "3") (pinfunction "S_3") (pintype "passive"))
      (node (ref "U6") (pin "3") (pinfunction "S_3") (pintype "passive"))
    )
    (net (code "56") (name "Vin") (class "Default")
      (node (ref "C10") (pin "2") (pinfunction "2_2") (pintype "passive"))
      (node (ref "C13") (pin "1") (pinfunction "1_1") (pintype "passive"))
      (node (ref "C14") (pin "1") (pinfunction "1_1") (pintype "passive"))
      (node (ref "C17") (pin "1") (pinfunction "1_1") (pintype "passive"))
      (node (ref "IC2") (pin "2") (pinfunction "V_IN_2") (pintype "passive"))
      (node (ref "IC2") (pin "4") (pinfunction "V_IN_4") (pintype "passive"))
      (node (ref "P2") (pin "1") (pinfunction "1_1") (pintype "passive"))
      (node (ref "P2") (pin "2") (pinfunction "2_2") (pintype "passive"))
      (node (ref "R8") (pin "2") (pinfunction "2_2") (pintype "passive"))
    )
    (net (code "57") (name "unconnected-(IC1-PA0{slash}WKUP1{slash}USART2_CTS{slash}ADC_IN0{slash}TIM2_CH1_ETR-Pad10)") (class "Default")
      (node (ref "IC1") (pin "10") (pinfunction "PA0/WKUP1/USART2_CTS/ADC_IN0/TIM2_CH1_ETR_10") (pintype "passive"))
    )
    (net (code "58") (name "unconnected-(IC1-PA8{slash}USART1_CK{slash}MCO{slash}LCD_COM0-Pad29)") (class "Default")
      (node (ref "IC1") (pin "29") (pinfunction "PA8/USART1_CK/MCO/LCD_COM0_29") (pintype "passive"))
    )
    (net (code "59") (name "unconnected-(IC1-PA11{slash}USART1_CTS{slash}USB_DM{slash}SPI1_MISO-Pad32)") (class "Default")
      (node (ref "IC1") (pin "32") (pinfunction "PA11/USART1_CTS/USB_DM/SPI1_MISO_32") (pintype "passive"))
    )
    (net (code "60") (name "unconnected-(IC1-PA12{slash}USART1_RTS{slash}USB_DP{slash}SPI1_MOSI-Pad33)") (class "Default")
      (node (ref "IC1") (pin "33") (pinfunction "PA12/USART1_RTS/USB_DP/SPI1_MOSI_33") (pintype "passive"))
    )
    (net (code "61") (name "unconnected-(IC1-PB4{slash}NJTRST{slash}TIM3_CH1{slash}SPI1_MISO{slash}COMP2_INP{slash}LCD_SEG8-Pad40)") (class "Default")
      (node (ref "IC1") (pin "40") (pinfunction "PB4/NJTRST/TIM3_CH1/SPI1_MISO/COMP2_INP/LCD_SEG8_40") (pintype "passive"))
    )
    (net (code "62") (name "unconnected-(IC1-PB5{slash}I2C1_SMBA{slash}TIM3_CH2{slash}SPI1_MOSI{slash}COMP2_INP{slash}LCD_SEG9-Pad41)") (class "Default")
      (node (ref "IC1") (pin "41") (pinfunction "PB5/I2C1_SMBA/TIM3_CH2/SPI1_MOSI/COMP2_INP/LCD_SEG9_41") (pintype "passive"))
    )
    (net (code "63") (name "unconnected-(IC1-PB15{slash}SPI2_MOSI{slash}LCD_SEG15{slash}ADC_IN21{slash}TIM11_CH1{slash}RTC_REFIN-Pad28)") (class "Default")
      (node (ref "IC1") (pin "28") (pinfunction "PB15/SPI2_MOSI/LCD_SEG15/ADC_IN21/TIM11_CH1/RTC_REFIN_28") (pintype "passive"))
    )
    (net (code "64") (name "unconnected-(IC1-PC13{slash}RTC_TAMP1{slash}RTC_TS{slash}RTC_OUT{slash}WKUP2-Pad2)") (class "Default")
      (node (ref "IC1") (pin "2") (pinfunction "PC13/RTC_TAMP1/RTC_TS/RTC_OUT/WKUP2_2") (pintype "passive"))
    )
    (net (code "65") (name "unconnected-(IC1-PC14{slash}OSC32_IN-Pad3)") (class "Default")
      (node (ref "IC1") (pin "3") (pinfunction "PC14/OSC32_IN_3") (pintype "passive"))
    )
    (net (code "66") (name "unconnected-(IC1-PC15{slash}OSC32_OUT-Pad4)") (class "Default")
      (node (ref "IC1") (pin "4") (pinfunction "PC15/OSC32_OUT_4") (pintype "passive"))
    )
    (net (code "67") (name "unconnected-(IC1-PH0{slash}OSC_IN-Pad5)") (class "Default")
      (node (ref "IC1") (pin "5") (pinfunction "PH0/OSC_IN_5") (pintype "passive"))
    )
    (net (code "68") (name "unconnected-(IC1-PH1{slash}OSC_OUT-Pad6)") (class "Default")
      (node (ref "IC1") (pin "6") (pinfunction "PH1/OSC_OUT_6") (pintype "passive"))
    )
    (net (code "69") (name "unconnected-(P2-Pad10)") (class "Default")
      (node (ref "P2") (pin "10") (pinfunction "10_10") (pintype "passive"))
    )
    (net (code "70") (name "unconnected-(U2-MISO-Pad8)") (class "Default")
      (node (ref "U2") (pin "8") (pinfunction "MISO_8") (pintype "passive"))
    )
    (net (code "71") (name "unconnected-(U2-MOSI-Pad9)") (class "Default")
      (node (ref "U2") (pin "9") (pinfunction "MOSI_9") (pintype "passive"))
    )
    (net (code "72") (name "unconnected-(U2-NSS-Pad6)") (class "Default")
      (node (ref "U2") (pin "6") (pinfunction "NSS_6") (pintype "passive"))
    )
    (net (code "73") (name "unconnected-(U2-PA3-Pad20)") (class "Default")
      (node (ref "U2") (pin "20") (pinfunction "PA3_20") (pintype "passive"))
    )
    (net (code "74") (name "unconnected-(U2-PA8-Pad3)") (class "Default")
      (node (ref "U2") (pin "3") (pinfunction "PA8_3") (pintype "passive"))
    )
    (net (code "75") (name "unconnected-(U2-PB3-Pad15)") (class "Default")
      (node (ref "U2") (pin "15") (pinfunction "PB3_15") (pintype "passive"))
    )
    (net (code "76") (name "unconnected-(U2-PC13-Pad26)") (class "Default")
      (node (ref "U2") (pin "26") (pinfunction "PC13_26") (pintype "passive"))
    )
    (net (code "77") (name "unconnected-(U2-RFIO_HF-Pad30)") (class "Default")
      (node (ref "U2") (pin "30") (pinfunction "RFIO_HF_30") (pintype "passive"))
    )
    (net (code "78") (name "unconnected-(U2-SCK-Pad7)") (class "Default")
      (node (ref "U2") (pin "7") (pinfunction "SCK_7") (pintype "passive"))
    )
    (net (code "79") (name "unconnected-(U2-SCL-Pad24)") (class "Default")
      (node (ref "U2") (pin "24") (pinfunction "SCL_24") (pintype "passive"))
    )
    (net (code "80") (name "unconnected-(U2-SDA-Pad25)") (class "Default")
      (node (ref "U2") (pin "25") (pinfunction "SDA_25") (pintype "passive"))
    )
    (net (code "81") (name "unconnected-(U2-USART_CTS-Pad10)") (class "Default")
      (node (ref "U2") (pin "10") (pinfunction "USART_CTS_10") (pintype "passive"))
    )
    (net (code "82") (name "unconnected-(U2-USART_RTS-Pad11)") (class "Default")
      (node (ref "U2") (pin "11") (pinfunction "USART_RTS_11") (pintype "passive"))
    )
  )
)
